# circuit-ldc-front-connector-hw.net
KiCad netlist of a schematic drawn in Altium Designer
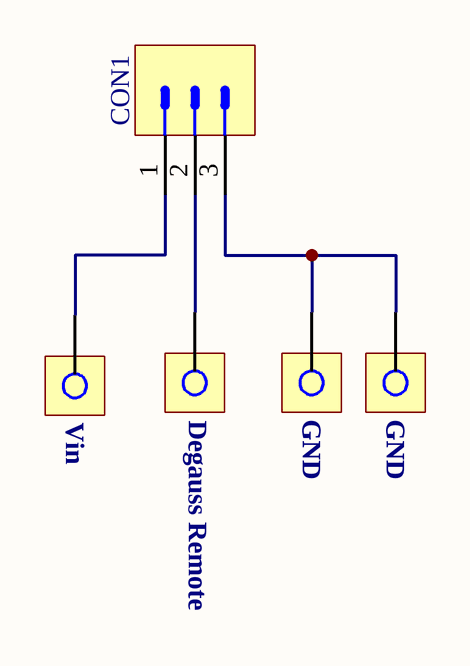
[diagram p0: circuit-ldc-front-connector-hw.SchDoc]

(export (version "E")
  (design (tool "Eeschema 10.0.6"))
  (components
    (comp (ref "CON1")
      (value "Connector 3 Male")
      (footprint "PHOENIX_1803439")
      (description "Header; 8 A; 160 V; 3.81; 3; Soldering; 1.2 mm; 2.5 kV; 160/250 V; PBT")
      (fields
        (field (name "MANUFACTURER") "Phoenix Contact")
        (field (name "MANUFACTURER PART NUMBER") "1803439")
      )
      (libsource (lib "ldc-front-connector-hw-library-schematic") (part "Connector 3 Male"))
    )
    (comp (ref "WH1")
      (value "WIRE HOLE")
      (footprint "WIRE HOLE")
      (libsource (lib "ldc-front-connector-hw-library-schematic") (part "WIRE HOLE"))
    )
    (comp (ref "WH2")
      (value "WIRE HOLE")
      (footprint "WIRE HOLE")
      (libsource (lib "ldc-front-connector-hw-library-schematic") (part "WIRE HOLE"))
    )
    (comp (ref "WH3")
      (value "WIRE HOLE")
      (footprint "WIRE HOLE")
      (libsource (lib "ldc-front-connector-hw-library-schematic") (part "WIRE HOLE"))
    )
    (comp (ref "WH4")
      (value "WIRE HOLE")
      (footprint "WIRE HOLE")
      (libsource (lib "ldc-front-connector-hw-library-schematic") (part "WIRE HOLE"))
    )
  )
  (nets
    (net (code "1") (name "Net-(CON1-Pad1)") (class "Default")
      (node (ref "CON1") (pin "1") (pinfunction "1_1") (pintype "passive"))
      (node (ref "WH1") (pin "1") (pinfunction "1_1") (pintype "passive"))
    )
    (net (code "2") (name "Net-(CON1-Pad2)") (class "Default")
      (node (ref "CON1") (pin "2") (pinfunction "2_2") (pintype "passive"))
      (node (ref "WH2") (pin "1") (pinfunction "1_1") (pintype "passive"))
    )
    (net (code "3") (name "Net-(CON1-Pad3)") (class "Default")
      (node (ref "CON1") (pin "3") (pinfunction "3_3") (pintype "passive"))
      (node (ref "WH3") (pin "1") (pinfunction "1_1") (pintype "passive"))
      (node (ref "WH4") (pin "1") (pinfunction "1_1") (pintype "passive"))
    )
  )
)
